# pic16f1619_OLED_I2C.net
KiCad netlist of a schematic drawn in EAGLE
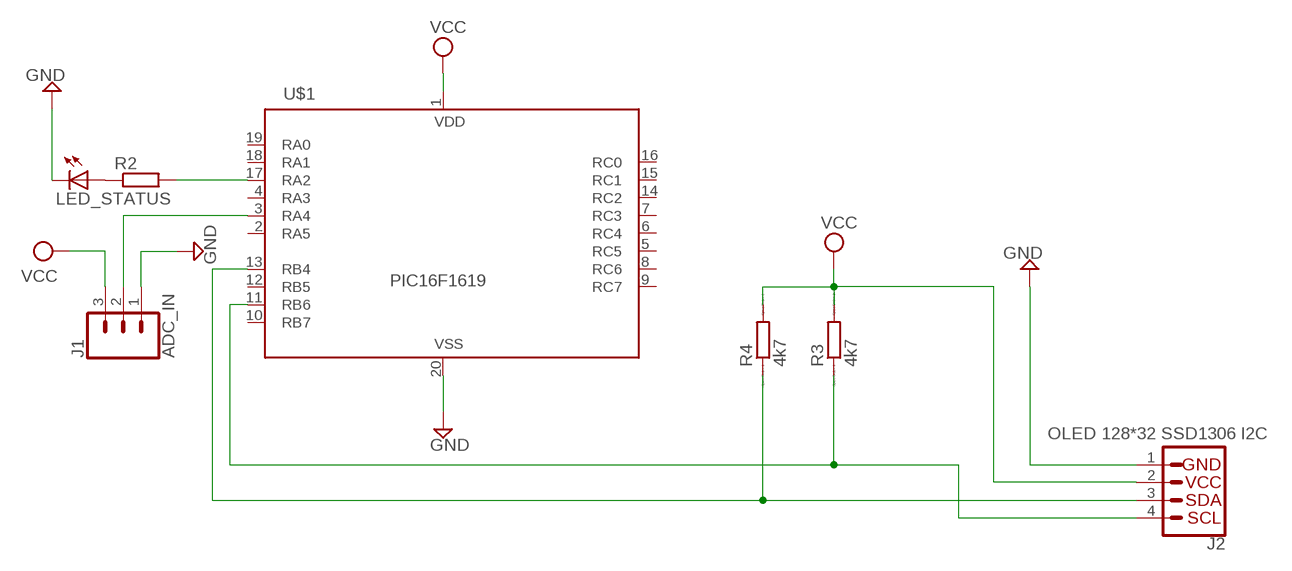
[diagram p0: schematic, sheet 1]

(export (version "E")
  (design (tool "Eeschema 10.0.6"))
  (components
    (comp (ref "J1")
      (value "ADC_IN")
      (footprint "eagle-import:1X03_LOCK")
      (libsource (lib "eagle-import") (part "CONN_03LOCK"))
    )
    (comp (ref "J2")
      (value "OLED 128*32 SSD1306 I2C")
      (footprint "eagle-import:1X04")
      (libsource (lib "eagle-import") (part "I2C_STANDARD"))
    )
    (comp (ref "LED_STATUS")
      (value "LEDB155")
      (footprint "eagle-import:Q62902-B155")
      (libsource (lib "eagle-import") (part "LEDB155"))
    )
    (comp (ref "R2")
      (value "R-EU_0309/V")
      (footprint "eagle-import:0309V")
      (libsource (lib "eagle-import") (part "R-EU_0309/V"))
    )
    (comp (ref "R3")
      (value "4k7")
      (footprint "eagle-import:R2010")
      (libsource (lib "eagle-import") (part "RR2010"))
    )
    (comp (ref "R4")
      (value "4k7")
      (footprint "eagle-import:R2010")
      (libsource (lib "eagle-import") (part "RR2010"))
    )
    (comp (ref "U$1")
      (value "PIC16F1619")
      (footprint "eagle-import:DIP20B")
      (libsource (lib "eagle-import") (part "PIC16F1619-DIP"))
    )
  )
  (nets
    (net (code "1") (name "GND") (class "Default")
      (node (ref "J1") (pin "1") (pinfunction "1_1") (pintype "passive"))
      (node (ref "J2") (pin "1") (pinfunction "1_1") (pintype "power_in"))
      (node (ref "LED_STATUS") (pin "K") (pinfunction "C_K") (pintype "passive"))
      (node (ref "U$1") (pin "20") (pinfunction "VSS_20") (pintype "power_in"))
    )
    (net (code "2") (name "Net-(LED_STATUS-PadA)") (class "Default")
      (node (ref "LED_STATUS") (pin "A") (pinfunction "A_A") (pintype "passive"))
      (node (ref "R2") (pin "1") (pinfunction "1_1") (pintype "passive"))
    )
    (net (code "3") (name "Net-(U$1-RA2)") (class "Default")
      (node (ref "R2") (pin "2") (pinfunction "2_2") (pintype "passive"))
      (node (ref "U$1") (pin "17") (pinfunction "RA2_17") (pintype "bidirectional"))
    )
    (net (code "4") (name "Net-(U$1-RA4)") (class "Default")
      (node (ref "J1") (pin "2") (pinfunction "2_2") (pintype "passive"))
      (node (ref "U$1") (pin "3") (pinfunction "RA4_3") (pintype "bidirectional"))
    )
    (net (code "5") (name "Net-(U$1-RB4)") (class "Default")
      (node (ref "J2") (pin "3") (pinfunction "3_3") (pintype "passive"))
      (node (ref "R4") (pin "1") (pinfunction "1_1") (pintype "passive"))
      (node (ref "U$1") (pin "13") (pinfunction "RB4_13") (pintype "bidirectional"))
    )
    (net (code "6") (name "Net-(U$1-RB6)") (class "Default")
      (node (ref "J2") (pin "4") (pinfunction "4_4") (pintype "passive"))
      (node (ref "R3") (pin "1") (pinfunction "1_1") (pintype "passive"))
      (node (ref "U$1") (pin "11") (pinfunction "RB6_11") (pintype "bidirectional"))
    )
    (net (code "7") (name "VCC") (class "Default")
      (node (ref "J1") (pin "3") (pinfunction "3_3") (pintype "passive"))
      (node (ref "J2") (pin "2") (pinfunction "2_2") (pintype "power_in"))
      (node (ref "R3") (pin "2") (pinfunction "2_2") (pintype "passive"))
      (node (ref "R4") (pin "2") (pinfunction "2_2") (pintype "passive"))
      (node (ref "U$1") (pin "1") (pinfunction "VDD_1") (pintype "power_in"))
    )
    (net (code "8") (name "unconnected-(U$1-RA0-Pad19)") (class "Default")
      (node (ref "U$1") (pin "19") (pinfunction "RA0_19") (pintype "bidirectional"))
    )
    (net (code "9") (name "unconnected-(U$1-RA1-Pad18)") (class "Default")
      (node (ref "U$1") (pin "18") (pinfunction "RA1_18") (pintype "bidirectional"))
    )
    (net (code "10") (name "unconnected-(U$1-RA3-Pad4)") (class "Default")
      (node (ref "U$1") (pin "4") (pinfunction "RA3_4") (pintype "input"))
    )
    (net (code "11") (name "unconnected-(U$1-RA5-Pad2)") (class "Default")
      (node (ref "U$1") (pin "2") (pinfunction "RA5_2") (pintype "bidirectional"))
    )
    (net (code "12") (name "unconnected-(U$1-RB5-Pad12)") (class "Default")
      (node (ref "U$1") (pin "12") (pinfunction "RB5_12") (pintype "bidirectional"))
    )
    (net (code "13") (name "unconnected-(U$1-RB7-Pad10)") (class "Default")
      (node (ref "U$1") (pin "10") (pinfunction "RB7_10") (pintype "bidirectional"))
    )
    (net (code "14") (name "unconnected-(U$1-RC0-Pad16)") (class "Default")
      (node (ref "U$1") (pin "16") (pinfunction "RC0_16") (pintype "bidirectional"))
    )
    (net (code "15") (name "unconnected-(U$1-RC1-Pad15)") (class "Default")
      (node (ref "U$1") (pin "15") (pinfunction "RC1_15") (pintype "bidirectional"))
    )
    (net (code "16") (name "unconnected-(U$1-RC2-Pad14)") (class "Default")
      (node (ref "U$1") (pin "14") (pinfunction "RC2_14") (pintype "bidirectional"))
    )
    (net (code "17") (name "unconnected-(U$1-RC3-Pad7)") (class "Default")
      (node (ref "U$1") (pin "7") (pinfunction "RC3_7") (pintype "bidirectional"))
    )
    (net (code "18") (name "unconnected-(U$1-RC4-Pad6)") (class "Default")
      (node (ref "U$1") (pin "6") (pinfunction "RC4_6") (pintype "bidirectional"))
    )
    (net (code "19") (name "unconnected-(U$1-RC5-Pad5)") (class "Default")
      (node (ref "U$1") (pin "5") (pinfunction "RC5_5") (pintype "bidirectional"))
    )
    (net (code "20") (name "unconnected-(U$1-RC6-Pad8)") (class "Default")
      (node (ref "U$1") (pin "8") (pinfunction "RC6_8") (pintype "bidirectional"))
    )
    (net (code "21") (name "unconnected-(U$1-RC7-Pad9)") (class "Default")
      (node (ref "U$1") (pin "9") (pinfunction "RC7_9") (pintype "bidirectional"))
    )
  )
)
